# main.net
KiCad netlist of a schematic drawn in EAGLE
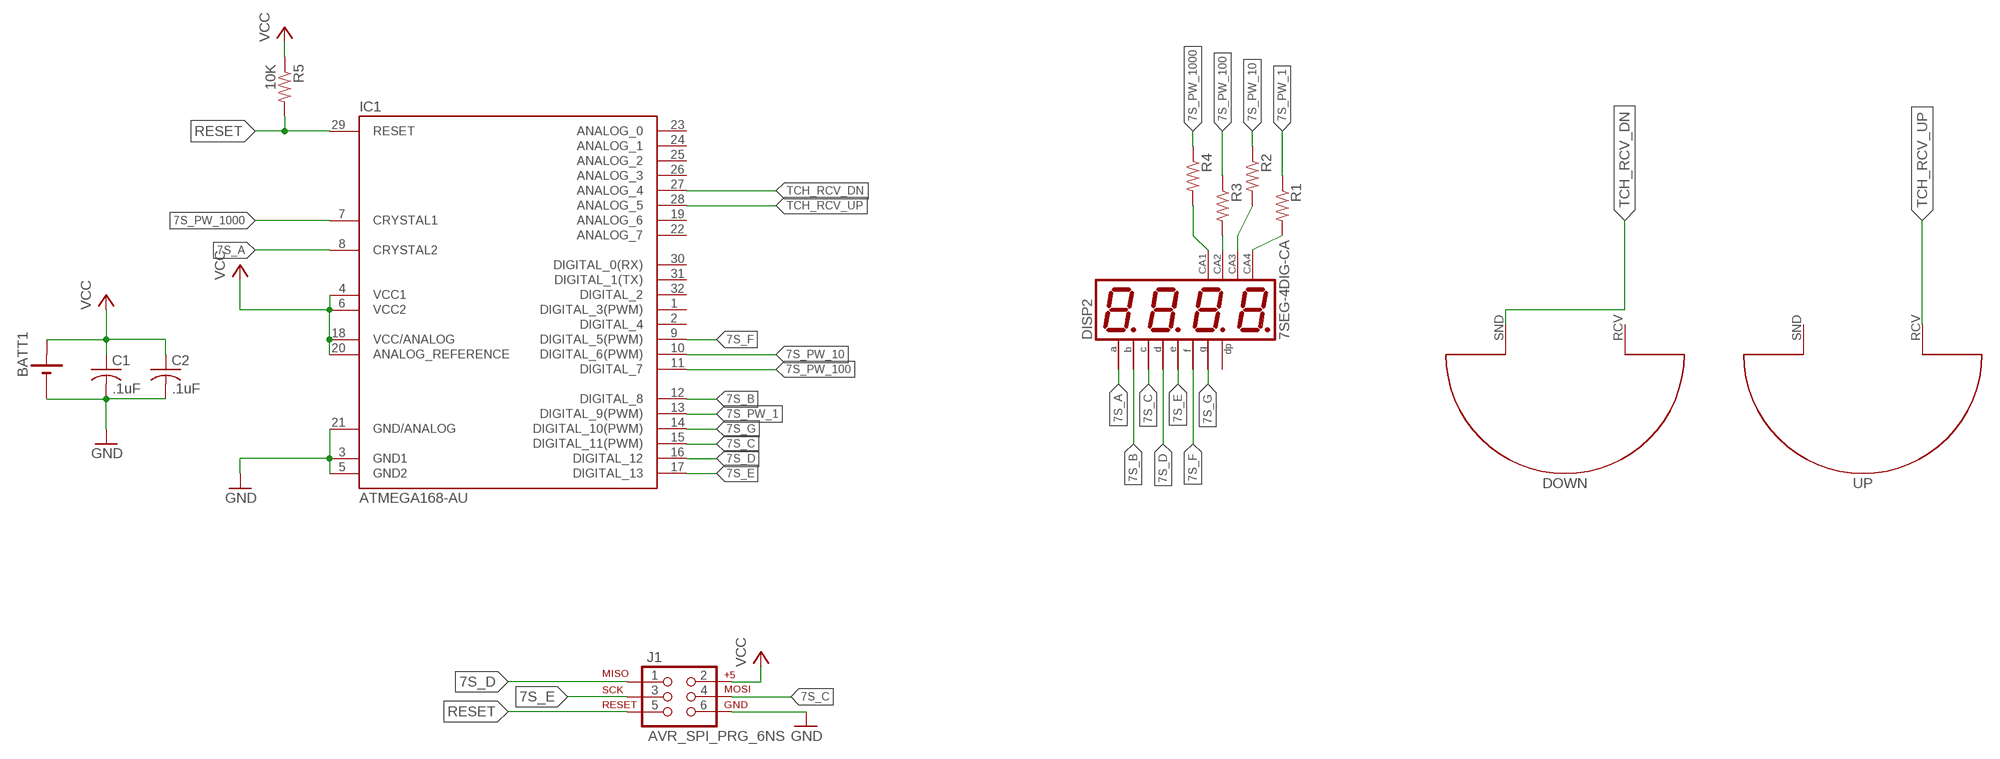
[diagram p0: schematic, sheet 1]

(export (version "E")
  (design (tool "Eeschema 10.0.6"))
  (components
    (comp (ref "BATT1")
      (value "2032SMD")
      (footprint "eagle-import:2032SMD")
      (libsource (lib "eagle-import") (part "2032SMD"))
    )
    (comp (ref "C1")
      (value ".1uF")
      (footprint "eagle-import:C0603")
      (libsource (lib "eagle-import") (part "C-USC0603"))
    )
    (comp (ref "C2")
      (value ".1uF")
      (footprint "eagle-import:C0603")
      (libsource (lib "eagle-import") (part "C-USC0603"))
    )
    (comp (ref "DISP2")
      (value "7SEG-4DIG-CA")
      (footprint "eagle-import:7SEG-0.36-4")
      (libsource (lib "eagle-import") (part "7SEG-4DIG-CA"))
    )
    (comp (ref "DOWN")
      (value "AVD-TCH-01")
      (footprint "eagle-import:AVD-TCH-01")
      (libsource (lib "eagle-import") (part "AVD-TCH-01"))
    )
    (comp (ref "IC1")
      (value "ATMEGA168-AU")
      (footprint "eagle-import:TQFP32-08")
      (libsource (lib "eagle-import") (part "ATMEGA168-AU"))
    )
    (comp (ref "J1")
      (value "AVR_SPI_PRG_6NS")
      (footprint "eagle-import:2X3-NS")
      (libsource (lib "eagle-import") (part "AVR_SPI_PRG_6NS"))
    )
    (comp (ref "R1")
      (value "R-US_R0603")
      (footprint "eagle-import:R0603")
      (libsource (lib "eagle-import") (part "R-US_R0603"))
    )
    (comp (ref "R2")
      (value "R-US_R0603")
      (footprint "eagle-import:R0603")
      (libsource (lib "eagle-import") (part "R-US_R0603"))
    )
    (comp (ref "R3")
      (value "R-US_R0603")
      (footprint "eagle-import:R0603")
      (libsource (lib "eagle-import") (part "R-US_R0603"))
    )
    (comp (ref "R4")
      (value "R-US_R0603")
      (footprint "eagle-import:R0603")
      (libsource (lib "eagle-import") (part "R-US_R0603"))
    )
    (comp (ref "R5")
      (value "10K")
      (footprint "eagle-import:R0603")
      (libsource (lib "eagle-import") (part "R-US_R0603"))
    )
    (comp (ref "UP")
      (value "AVD-TCH-01")
      (footprint "eagle-import:AVD-TCH-01")
      (libsource (lib "eagle-import") (part "AVD-TCH-01"))
    )
  )
  (nets
    (net (code "1") (name "7S_A") (class "Default")
      (node (ref "DISP2") (pin "11") (pinfunction "A_11") (pintype "passive"))
      (node (ref "IC1") (pin "8") (pinfunction "CRYSTAL2_8") (pintype "bidirectional"))
    )
    (net (code "2") (name "7S_B") (class "Default")
      (node (ref "DISP2") (pin "7") (pinfunction "B_7") (pintype "passive"))
      (node (ref "IC1") (pin "12") (pinfunction "DIGITAL_8_12") (pintype "bidirectional"))
    )
    (net (code "3") (name "7S_C") (class "Default")
      (node (ref "DISP2") (pin "4") (pinfunction "C_4") (pintype "passive"))
      (node (ref "IC1") (pin "15") (pinfunction "DIGITAL_11(PWM)_15") (pintype "bidirectional"))
      (node (ref "J1") (pin "4") (pinfunction "4_4") (pintype "passive"))
    )
    (net (code "4") (name "7S_D") (class "Default")
      (node (ref "DISP2") (pin "2") (pinfunction "D_2") (pintype "passive"))
      (node (ref "IC1") (pin "16") (pinfunction "DIGITAL_12_16") (pintype "bidirectional"))
      (node (ref "J1") (pin "1") (pinfunction "1_1") (pintype "passive"))
    )
    (net (code "5") (name "7S_E") (class "Default")
      (node (ref "DISP2") (pin "1") (pinfunction "E_1") (pintype "passive"))
      (node (ref "IC1") (pin "17") (pinfunction "DIGITAL_13_17") (pintype "bidirectional"))
      (node (ref "J1") (pin "3") (pinfunction "3_3") (pintype "passive"))
    )
    (net (code "6") (name "7S_F") (class "Default")
      (node (ref "DISP2") (pin "10") (pinfunction "F_10") (pintype "passive"))
      (node (ref "IC1") (pin "9") (pinfunction "DIGITAL_5(PWM)_9") (pintype "bidirectional"))
    )
    (net (code "7") (name "7S_G") (class "Default")
      (node (ref "DISP2") (pin "5") (pinfunction "G_5") (pintype "passive"))
      (node (ref "IC1") (pin "14") (pinfunction "DIGITAL_10(PWM)_14") (pintype "bidirectional"))
    )
    (net (code "8") (name "7S_PW_1") (class "Default")
      (node (ref "IC1") (pin "13") (pinfunction "DIGITAL_9(PWM)_13") (pintype "bidirectional"))
      (node (ref "R1") (pin "1") (pinfunction "1_1") (pintype "passive"))
    )
    (net (code "9") (name "7S_PW_10") (class "Default")
      (node (ref "IC1") (pin "10") (pinfunction "DIGITAL_6(PWM)_10") (pintype "bidirectional"))
      (node (ref "R2") (pin "1") (pinfunction "1_1") (pintype "passive"))
    )
    (net (code "10") (name "7S_PW_100") (class "Default")
      (node (ref "IC1") (pin "11") (pinfunction "DIGITAL_7_11") (pintype "bidirectional"))
      (node (ref "R3") (pin "1") (pinfunction "1_1") (pintype "passive"))
    )
    (net (code "11") (name "7S_PW_1000") (class "Default")
      (node (ref "IC1") (pin "7") (pinfunction "CRYSTAL1_7") (pintype "bidirectional"))
      (node (ref "R4") (pin "1") (pinfunction "1_1") (pintype "passive"))
    )
    (net (code "12") (name "GND") (class "Default")
      (node (ref "BATT1") (pin "-") (pinfunction "-_-") (pintype "passive"))
      (node (ref "C1") (pin "2") (pinfunction "2_2") (pintype "passive"))
      (node (ref "C2") (pin "2") (pinfunction "2_2") (pintype "passive"))
      (node (ref "IC1") (pin "21") (pinfunction "GND/ANALOG_21") (pintype "power_in"))
      (node (ref "IC1") (pin "3") (pinfunction "GND1_3") (pintype "power_in"))
      (node (ref "IC1") (pin "5") (pinfunction "GND2_5") (pintype "power_in"))
      (node (ref "J1") (pin "6") (pinfunction "6_6") (pintype "passive"))
    )
    (net (code "13") (name "Net-(DISP2-CA1)") (class "Default")
      (node (ref "DISP2") (pin "12") (pinfunction "CA1_12") (pintype "passive"))
      (node (ref "R4") (pin "2") (pinfunction "2_2") (pintype "passive"))
    )
    (net (code "14") (name "Net-(DISP2-CA2)") (class "Default")
      (node (ref "DISP2") (pin "9") (pinfunction "CA2_9") (pintype "passive"))
      (node (ref "R3") (pin "2") (pinfunction "2_2") (pintype "passive"))
    )
    (net (code "15") (name "Net-(DISP2-CA3)") (class "Default")
      (node (ref "DISP2") (pin "8") (pinfunction "CA3_8") (pintype "passive"))
      (node (ref "R2") (pin "2") (pinfunction "2_2") (pintype "passive"))
    )
    (net (code "16") (name "Net-(DISP2-CA4)") (class "Default")
      (node (ref "DISP2") (pin "6") (pinfunction "CA4_6") (pintype "passive"))
      (node (ref "R1") (pin "2") (pinfunction "2_2") (pintype "passive"))
    )
    (net (code "17") (name "RESET") (class "Default")
      (node (ref "IC1") (pin "29") (pinfunction "RESET_29") (pintype "bidirectional"))
      (node (ref "J1") (pin "5") (pinfunction "5_5") (pintype "passive"))
      (node (ref "R5") (pin "2") (pinfunction "2_2") (pintype "passive"))
    )
    (net (code "18") (name "TCH_RCV_DN") (class "Default")
      (node (ref "DOWN") (pin "SND") (pinfunction "SND_SND") (pintype "bidirectional"))
      (node (ref "IC1") (pin "27") (pinfunction "ANALOG_4_27") (pintype "bidirectional"))
    )
    (net (code "19") (name "TCH_RCV_UP") (class "Default")
      (node (ref "IC1") (pin "28") (pinfunction "ANALOG_5_28") (pintype "bidirectional"))
      (node (ref "UP") (pin "RCV") (pinfunction "RCV_RCV") (pintype "bidirectional"))
    )
    (net (code "20") (name "VCC") (class "Default")
      (node (ref "BATT1") (pin "+") (pinfunction "+_+") (pintype "passive"))
      (node (ref "C1") (pin "1") (pinfunction "1_1") (pintype "passive"))
      (node (ref "C2") (pin "1") (pinfunction "1_1") (pintype "passive"))
      (node (ref "IC1") (pin "18") (pinfunction "VCC/ANALOG_18") (pintype "passive"))
      (node (ref "IC1") (pin "20") (pinfunction "ANALOG_REFERENCE_20") (pintype "passive"))
      (node (ref "IC1") (pin "4") (pinfunction "VCC1_4") (pintype "power_in"))
      (node (ref "IC1") (pin "6") (pinfunction "VCC2_6") (pintype "power_in"))
      (node (ref "J1") (pin "2") (pinfunction "2_2") (pintype "passive"))
      (node (ref "R5") (pin "1") (pinfunction "1_1") (pintype "passive"))
    )
    (net (code "21") (name "unconnected-(DISP2-DP-Pad3)") (class "Default")
      (node (ref "DISP2") (pin "3") (pinfunction "DP_3") (pintype "passive"))
    )
    (net (code "22") (name "unconnected-(DOWN-PadRCV)") (class "Default")
      (node (ref "DOWN") (pin "RCV") (pinfunction "RCV_RCV") (pintype "bidirectional"))
    )
    (net (code "23") (name "unconnected-(IC1-ANALOG_0-Pad23)") (class "Default")
      (node (ref "IC1") (pin "23") (pinfunction "ANALOG_0_23") (pintype "bidirectional"))
    )
    (net (code "24") (name "unconnected-(IC1-ANALOG_1-Pad24)") (class "Default")
      (node (ref "IC1") (pin "24") (pinfunction "ANALOG_1_24") (pintype "bidirectional"))
    )
    (net (code "25") (name "unconnected-(IC1-ANALOG_2-Pad25)") (class "Default")
      (node (ref "IC1") (pin "25") (pinfunction "ANALOG_2_25") (pintype "bidirectional"))
    )
    (net (code "26") (name "unconnected-(IC1-ANALOG_3-Pad26)") (class "Default")
      (node (ref "IC1") (pin "26") (pinfunction "ANALOG_3_26") (pintype "bidirectional"))
    )
    (net (code "27") (name "unconnected-(IC1-ANALOG_6-Pad19)") (class "Default")
      (node (ref "IC1") (pin "19") (pinfunction "ANALOG_6_19") (pintype "passive"))
    )
    (net (code "28") (name "unconnected-(IC1-ANALOG_7-Pad22)") (class "Default")
      (node (ref "IC1") (pin "22") (pinfunction "ANALOG_7_22") (pintype "passive"))
    )
    (net (code "29") (name "unconnected-(IC1-DIGITAL_0(RX)-Pad30)") (class "Default")
      (node (ref "IC1") (pin "30") (pinfunction "DIGITAL_0(RX)_30") (pintype "bidirectional"))
    )
    (net (code "30") (name "unconnected-(IC1-DIGITAL_1(TX)-Pad31)") (class "Default")
      (node (ref "IC1") (pin "31") (pinfunction "DIGITAL_1(TX)_31") (pintype "bidirectional"))
    )
    (net (code "31") (name "unconnected-(IC1-DIGITAL_2-Pad32)") (class "Default")
      (node (ref "IC1") (pin "32") (pinfunction "DIGITAL_2_32") (pintype "bidirectional"))
    )
    (net (code "32") (name "unconnected-(IC1-DIGITAL_3(PWM)-Pad1)") (class "Default")
      (node (ref "IC1") (pin "1") (pinfunction "DIGITAL_3(PWM)_1") (pintype "bidirectional"))
    )
    (net (code "33") (name "unconnected-(IC1-DIGITAL_4-Pad2)") (class "Default")
      (node (ref "IC1") (pin "2") (pinfunction "DIGITAL_4_2") (pintype "bidirectional"))
    )
    (net (code "34") (name "unconnected-(UP-PadSND)") (class "Default")
      (node (ref "UP") (pin "SND") (pinfunction "SND_SND") (pintype "bidirectional"))
    )
  )
)
